# Charger.net
KiCad netlist of a schematic drawn in EAGLE
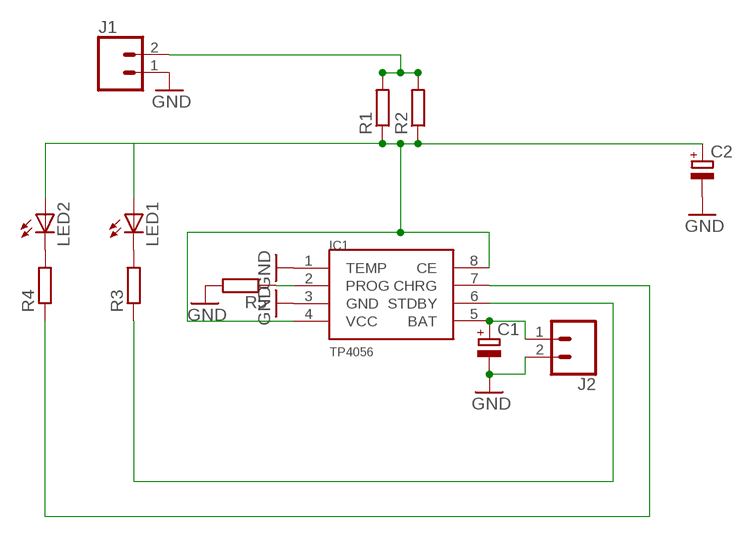
[diagram p0: schematic, sheet 1]

(export (version "E")
  (design (tool "Eeschema 10.0.6"))
  (components
    (comp (ref "C1")
      (value "CPOL-EUE2.5-7")
      (footprint "eagle-import:E2,5-7")
      (libsource (lib "eagle-import") (part "CPOL-EUE2.5-7"))
    )
    (comp (ref "C2")
      (value "CPOL-EUE2.5-7")
      (footprint "eagle-import:E2,5-7")
      (libsource (lib "eagle-import") (part "CPOL-EUE2.5-7"))
    )
    (comp (ref "IC1")
      (value "TP4056")
      (footprint "eagle-import:SOP-8")
      (libsource (lib "eagle-import") (part "TP4056"))
    )
    (comp (ref "J1")
      (value "CONN_02PTH4")
      (footprint "eagle-import:1X02_XTRA_BIG")
      (libsource (lib "eagle-import") (part "CONN_02PTH4"))
    )
    (comp (ref "J2")
      (value "CONN_02PTH4")
      (footprint "eagle-import:1X02_XTRA_BIG")
      (libsource (lib "eagle-import") (part "CONN_02PTH4"))
    )
    (comp (ref "LED1")
      (value "LED5MM")
      (footprint "eagle-import:LED5MM")
      (libsource (lib "eagle-import") (part "LED5MM"))
    )
    (comp (ref "LED2")
      (value "LED5MM")
      (footprint "eagle-import:LED5MM")
      (libsource (lib "eagle-import") (part "LED5MM"))
    )
    (comp (ref "R1")
      (value "R-EU_R1206")
      (footprint "eagle-import:R1206")
      (libsource (lib "eagle-import") (part "R-EU_R1206"))
    )
    (comp (ref "R2")
      (value "R-EU_R1206")
      (footprint "eagle-import:R1206")
      (libsource (lib "eagle-import") (part "R-EU_R1206"))
    )
    (comp (ref "R3")
      (value "R-EU_R1206")
      (footprint "eagle-import:R1206")
      (libsource (lib "eagle-import") (part "R-EU_R1206"))
    )
    (comp (ref "R4")
      (value "R-EU_R1206")
      (footprint "eagle-import:R1206")
      (libsource (lib "eagle-import") (part "R-EU_R1206"))
    )
    (comp (ref "R5")
      (value "R-EU_R1206")
      (footprint "eagle-import:R1206")
      (libsource (lib "eagle-import") (part "R-EU_R1206"))
    )
  )
  (nets
    (net (code "1") (name "GND") (class "Default")
      (node (ref "C1") (pin "-") (pinfunction "-_-") (pintype "passive"))
      (node (ref "C2") (pin "-") (pinfunction "-_-") (pintype "passive"))
      (node (ref "IC1") (pin "1") (pinfunction "TEMP_1") (pintype "bidirectional"))
      (node (ref "IC1") (pin "3") (pinfunction "GND_3") (pintype "bidirectional"))
      (node (ref "J1") (pin "1") (pinfunction "1_1") (pintype "passive"))
      (node (ref "J2") (pin "2") (pinfunction "2_2") (pintype "passive"))
      (node (ref "R5") (pin "2") (pinfunction "2_2") (pintype "passive"))
    )
    (net (code "2") (name "Net-(IC1-BAT)") (class "Default")
      (node (ref "C1") (pin "+") (pinfunction "+_+") (pintype "passive"))
      (node (ref "IC1") (pin "5") (pinfunction "BAT_5") (pintype "bidirectional"))
      (node (ref "J2") (pin "1") (pinfunction "1_1") (pintype "passive"))
    )
    (net (code "3") (name "Net-(IC1-CE)") (class "Default")
      (node (ref "C2") (pin "+") (pinfunction "+_+") (pintype "passive"))
      (node (ref "IC1") (pin "4") (pinfunction "VCC_4") (pintype "bidirectional"))
      (node (ref "IC1") (pin "8") (pinfunction "CE_8") (pintype "bidirectional"))
      (node (ref "LED1") (pin "A") (pinfunction "A_A") (pintype "passive"))
      (node (ref "LED2") (pin "A") (pinfunction "A_A") (pintype "passive"))
      (node (ref "R1") (pin "1") (pinfunction "1_1") (pintype "passive"))
      (node (ref "R2") (pin "1") (pinfunction "1_1") (pintype "passive"))
    )
    (net (code "4") (name "Net-(IC1-CHRG)") (class "Default")
      (node (ref "IC1") (pin "7") (pinfunction "CHRG_7") (pintype "bidirectional"))
      (node (ref "R4") (pin "1") (pinfunction "1_1") (pintype "passive"))
    )
    (net (code "5") (name "Net-(IC1-PROG)") (class "Default")
      (node (ref "IC1") (pin "2") (pinfunction "PROG_2") (pintype "bidirectional"))
      (node (ref "R5") (pin "1") (pinfunction "1_1") (pintype "passive"))
    )
    (net (code "6") (name "Net-(IC1-STDBY)") (class "Default")
      (node (ref "IC1") (pin "6") (pinfunction "STDBY_6") (pintype "bidirectional"))
      (node (ref "R3") (pin "1") (pinfunction "1_1") (pintype "passive"))
    )
    (net (code "7") (name "Net-(J1-Pad2)") (class "Default")
      (node (ref "J1") (pin "2") (pinfunction "2_2") (pintype "passive"))
      (node (ref "R1") (pin "2") (pinfunction "2_2") (pintype "passive"))
      (node (ref "R2") (pin "2") (pinfunction "2_2") (pintype "passive"))
    )
    (net (code "8") (name "Net-(LED1-C)") (class "Default")
      (node (ref "LED1") (pin "K") (pinfunction "C_K") (pintype "passive"))
      (node (ref "R3") (pin "2") (pinfunction "2_2") (pintype "passive"))
    )
    (net (code "9") (name "Net-(LED2-C)") (class "Default")
      (node (ref "LED2") (pin "K") (pinfunction "C_K") (pintype "passive"))
      (node (ref "R4") (pin "2") (pinfunction "2_2") (pintype "passive"))
    )
  )
)
